# Eitech-Robotics_v10dev.net
KiCad netlist of a schematic drawn in EAGLE
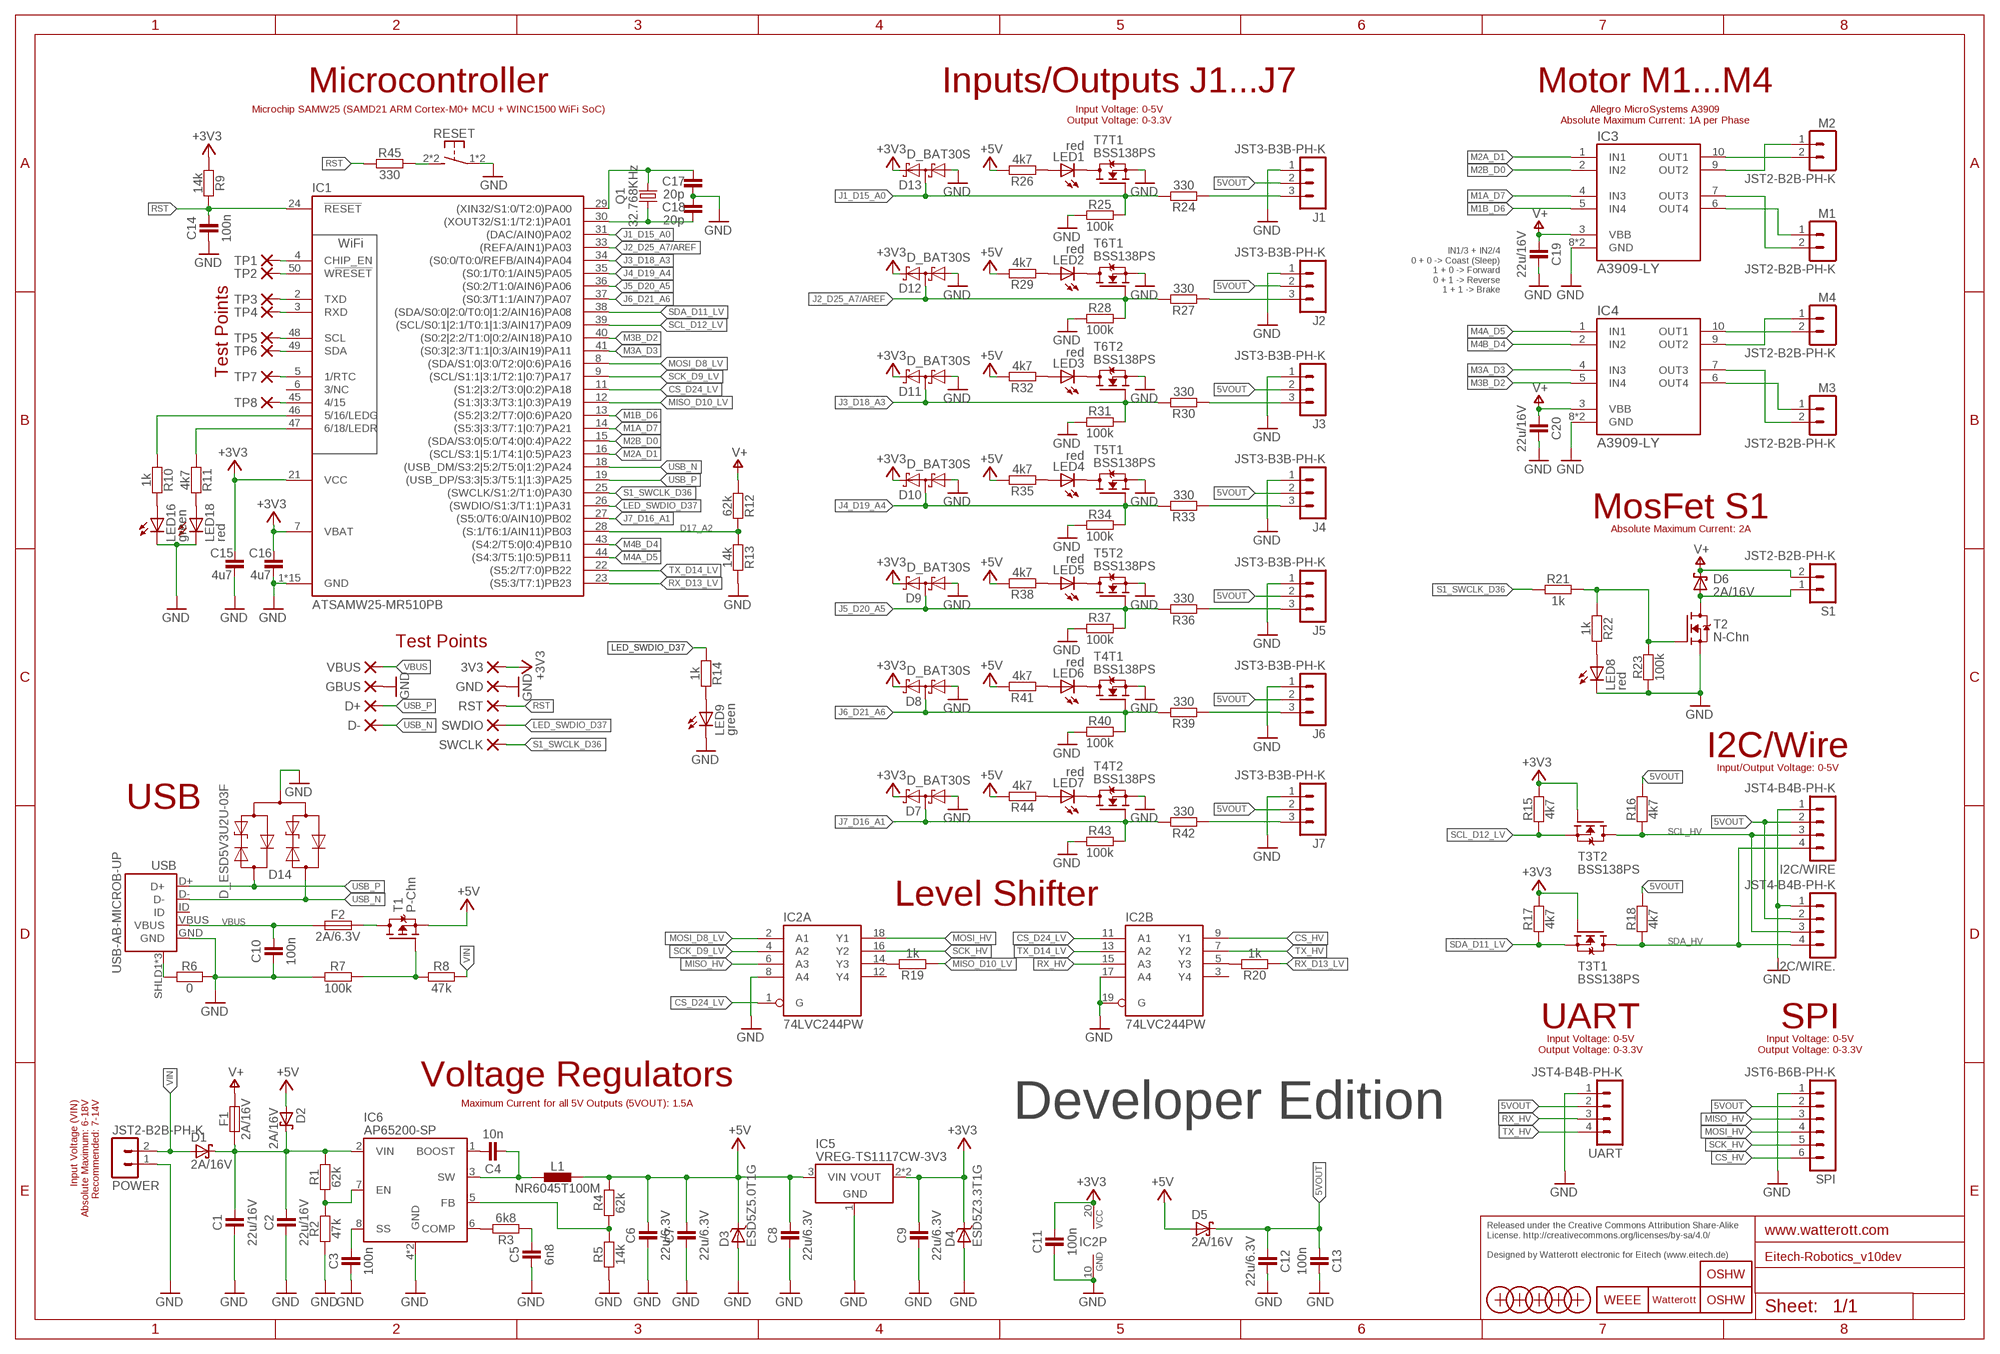
[diagram p0: schematic, sheet 1]

(export (version "E")
  (design (tool "Eeschema 10.0.6"))
  (components
    (comp (ref "3V3")
      (value "PAD-1.0_NC")
      (footprint "eagle-import:PAD-1.0_NC")
      (libsource (lib "eagle-import") (part "PAD-1.0_NC"))
    )
    (comp (ref "C1")
      (value "22u/16V")
      (footprint "eagle-import:C0805")
      (libsource (lib "eagle-import") (part "CAPACITOR-0805"))
    )
    (comp (ref "C2")
      (value "22u/16V")
      (footprint "eagle-import:C0805")
      (libsource (lib "eagle-import") (part "CAPACITOR-0805"))
    )
    (comp (ref "C3")
      (value "100n")
      (footprint "eagle-import:C0402")
      (libsource (lib "eagle-import") (part "CAPACITOR-0402"))
    )
    (comp (ref "C4")
      (value "10n")
      (footprint "eagle-import:C0402")
      (libsource (lib "eagle-import") (part "CAPACITOR-0402"))
    )
    (comp (ref "C5")
      (value "6n8")
      (footprint "eagle-import:C0402")
      (libsource (lib "eagle-import") (part "CAPACITOR-0402"))
    )
    (comp (ref "C6")
      (value "22u/6.3V")
      (footprint "eagle-import:C0805")
      (libsource (lib "eagle-import") (part "CAPACITOR-0805"))
    )
    (comp (ref "C7")
      (value "22u/6.3V")
      (footprint "eagle-import:C0805")
      (libsource (lib "eagle-import") (part "CAPACITOR-0805"))
    )
    (comp (ref "C8")
      (value "22u/6.3V")
      (footprint "eagle-import:C0805")
      (libsource (lib "eagle-import") (part "CAPACITOR-0805"))
    )
    (comp (ref "C9")
      (value "22u/6.3V")
      (footprint "eagle-import:C0805")
      (libsource (lib "eagle-import") (part "CAPACITOR-0805"))
    )
    (comp (ref "C10")
      (value "100n")
      (footprint "eagle-import:C0402")
      (libsource (lib "eagle-import") (part "CAPACITOR-0402"))
    )
    (comp (ref "C11")
      (value "100n")
      (footprint "eagle-import:C0402")
      (libsource (lib "eagle-import") (part "CAPACITOR-0402"))
    )
    (comp (ref "C12")
      (value "22u/6.3V")
      (footprint "eagle-import:C0805")
      (libsource (lib "eagle-import") (part "CAPACITOR-0805"))
    )
    (comp (ref "C13")
      (value "100n")
      (footprint "eagle-import:C0402")
      (libsource (lib "eagle-import") (part "CAPACITOR-0402"))
    )
    (comp (ref "C14")
      (value "100n")
      (footprint "eagle-import:C0402")
      (libsource (lib "eagle-import") (part "CAPACITOR-0402"))
    )
    (comp (ref "C15")
      (value "4u7")
      (footprint "eagle-import:C0603")
      (libsource (lib "eagle-import") (part "CAPACITOR-0603"))
    )
    (comp (ref "C16")
      (value "4u7")
      (footprint "eagle-import:C0603")
      (libsource (lib "eagle-import") (part "CAPACITOR-0603"))
    )
    (comp (ref "C17")
      (value "20p")
      (footprint "eagle-import:C0402")
      (libsource (lib "eagle-import") (part "CAPACITOR-0402"))
    )
    (comp (ref "C18")
      (value "20p")
      (footprint "eagle-import:C0402")
      (libsource (lib "eagle-import") (part "CAPACITOR-0402"))
    )
    (comp (ref "C19")
      (value "22u/16V")
      (footprint "eagle-import:C0805")
      (libsource (lib "eagle-import") (part "CAPACITOR-0805"))
    )
    (comp (ref "C20")
      (value "22u/16V")
      (footprint "eagle-import:C0805")
      (libsource (lib "eagle-import") (part "CAPACITOR-0805"))
    )
    (comp (ref "D+")
      (value "PAD-1.0_NC")
      (footprint "eagle-import:PAD-1.0_NC")
      (libsource (lib "eagle-import") (part "PAD-1.0_NC"))
    )
    (comp (ref "D-")
      (value "PAD-1.0_NC")
      (footprint "eagle-import:PAD-1.0_NC")
      (libsource (lib "eagle-import") (part "PAD-1.0_NC"))
    )
    (comp (ref "D1")
      (value "2A/16V")
      (footprint "eagle-import:SMA_DO214AC")
      (libsource (lib "eagle-import") (part "D_SCHOTTKY-SMA"))
    )
    (comp (ref "D2")
      (value "2A/16V")
      (footprint "eagle-import:SMA_DO214AC")
      (libsource (lib "eagle-import") (part "D_SCHOTTKY-SMA"))
    )
    (comp (ref "D3")
      (value "ESD5Z5.0T1G")
      (footprint "eagle-import:SOD523")
      (libsource (lib "eagle-import") (part "D_TVS-SOD523"))
    )
    (comp (ref "D4")
      (value "ESD5Z3.3T1G")
      (footprint "eagle-import:SOD523")
      (libsource (lib "eagle-import") (part "D_TVS-SOD523"))
    )
    (comp (ref "D5")
      (value "2A/16V")
      (footprint "eagle-import:SMA_DO214AC")
      (libsource (lib "eagle-import") (part "D_SCHOTTKY-SMA"))
    )
    (comp (ref "D6")
      (value "2A/16V")
      (footprint "eagle-import:SMA_DO214AC")
      (libsource (lib "eagle-import") (part "D_SCHOTTKY-SMA"))
    )
    (comp (ref "D7")
      (value "D_BAT30S")
      (footprint "eagle-import:SOT323")
      (libsource (lib "eagle-import") (part "D_BAT30S"))
    )
    (comp (ref "D8")
      (value "D_BAT30S")
      (footprint "eagle-import:SOT323")
      (libsource (lib "eagle-import") (part "D_BAT30S"))
    )
    (comp (ref "D9")
      (value "D_BAT30S")
      (footprint "eagle-import:SOT323")
      (libsource (lib "eagle-import") (part "D_BAT30S"))
    )
    (comp (ref "D10")
      (value "D_BAT30S")
      (footprint "eagle-import:SOT323")
      (libsource (lib "eagle-import") (part "D_BAT30S"))
    )
    (comp (ref "D11")
      (value "D_BAT30S")
      (footprint "eagle-import:SOT323")
      (libsource (lib "eagle-import") (part "D_BAT30S"))
    )
    (comp (ref "D12")
      (value "D_BAT30S")
      (footprint "eagle-import:SOT323")
      (libsource (lib "eagle-import") (part "D_BAT30S"))
    )
    (comp (ref "D13")
      (value "D_BAT30S")
      (footprint "eagle-import:SOT323")
      (libsource (lib "eagle-import") (part "D_BAT30S"))
    )
    (comp (ref "D14")
      (value "D_ESD5V3U2U-03F")
      (footprint "eagle-import:SOT723")
      (libsource (lib "eagle-import") (part "D_ESD5V3U2U-03F"))
    )
    (comp (ref "F1")
      (value "2A/16V")
      (footprint "eagle-import:C1812")
      (libsource (lib "eagle-import") (part "FUSE-1812"))
    )
    (comp (ref "F2")
      (value "2A/6.3V")
      (footprint "eagle-import:C1206")
      (libsource (lib "eagle-import") (part "FUSE-1206"))
    )
    (comp (ref "GBUS")
      (value "PAD-1.0_NC")
      (footprint "eagle-import:PAD-1.0_NC")
      (libsource (lib "eagle-import") (part "PAD-1.0_NC"))
    )
    (comp (ref "GND")
      (value "PAD-1.0_NC")
      (footprint "eagle-import:PAD-1.0_NC")
      (libsource (lib "eagle-import") (part "PAD-1.0_NC"))
    )
    (comp (ref "I2C/WIRE")
      (value "JST4-B4B-PH-K")
      (footprint "eagle-import:JST_B4B-PH-K")
      (libsource (lib "eagle-import") (part "JST4-B4B-PH-K"))
    )
    (comp (ref "I2C/WIRE.")
      (value "JST4-B4B-PH-K")
      (footprint "eagle-import:JST_B4B-PH-K")
      (libsource (lib "eagle-import") (part "JST4-B4B-PH-K"))
    )
    (comp (ref "IC1")
      (value "ATSAMW25-MR510PB")
      (footprint "eagle-import:ATSAMW25-MRX10")
      (libsource (lib "eagle-import") (part "ATSAMW25-MR510PB"))
    )
    (comp (ref "IC2")
      (value "74LVC244PW")
      (footprint "eagle-import:TSSOP20")
      (libsource (lib "eagle-import") (part "74244PWLVC"))
    )
    (comp (ref "IC3")
      (value "A3909-LY")
      (footprint "eagle-import:MSOP10-PAD")
      (libsource (lib "eagle-import") (part "A3909-LY"))
    )
    (comp (ref "IC4")
      (value "A3909-LY")
      (footprint "eagle-import:MSOP10-PAD")
      (libsource (lib "eagle-import") (part "A3909-LY"))
    )
    (comp (ref "IC5")
      (value "VREG-TS1117CW-3V3")
      (footprint "eagle-import:SOT223")
      (libsource (lib "eagle-import") (part "VREG-TS1117CW-3V3"))
    )
    (comp (ref "IC6")
      (value "AP65200-SP")
      (footprint "eagle-import:SO08-PAD")
      (libsource (lib "eagle-import") (part "AP65200-SP"))
    )
    (comp (ref "J1")
      (value "JST3-B3B-PH-K")
      (footprint "eagle-import:JST_B3B-PH-K")
      (libsource (lib "eagle-import") (part "JST3-B3B-PH-K"))
    )
    (comp (ref "J2")
      (value "JST3-B3B-PH-K")
      (footprint "eagle-import:JST_B3B-PH-K")
      (libsource (lib "eagle-import") (part "JST3-B3B-PH-K"))
    )
    (comp (ref "J3")
      (value "JST3-B3B-PH-K")
      (footprint "eagle-import:JST_B3B-PH-K")
      (libsource (lib "eagle-import") (part "JST3-B3B-PH-K"))
    )
    (comp (ref "J4")
      (value "JST3-B3B-PH-K")
      (footprint "eagle-import:JST_B3B-PH-K")
      (libsource (lib "eagle-import") (part "JST3-B3B-PH-K"))
    )
    (comp (ref "J5")
      (value "JST3-B3B-PH-K")
      (footprint "eagle-import:JST_B3B-PH-K")
      (libsource (lib "eagle-import") (part "JST3-B3B-PH-K"))
    )
    (comp (ref "J6")
      (value "JST3-B3B-PH-K")
      (footprint "eagle-import:JST_B3B-PH-K")
      (libsource (lib "eagle-import") (part "JST3-B3B-PH-K"))
    )
    (comp (ref "J7")
      (value "JST3-B3B-PH-K")
      (footprint "eagle-import:JST_B3B-PH-K")
      (libsource (lib "eagle-import") (part "JST3-B3B-PH-K"))
    )
    (comp (ref "L1")
      (value "NR6045T100M")
      (footprint "eagle-import:L_NR60XX")
      (libsource (lib "eagle-import") (part "INDUCTOR-NR60XX"))
    )
    (comp (ref "LED1")
      (value "red")
      (footprint "eagle-import:C0603")
      (libsource (lib "eagle-import") (part "LED-0603"))
    )
    (comp (ref "LED2")
      (value "red")
      (footprint "eagle-import:C0603")
      (libsource (lib "eagle-import") (part "LED-0603"))
    )
    (comp (ref "LED3")
      (value "red")
      (footprint "eagle-import:C0603")
      (libsource (lib "eagle-import") (part "LED-0603"))
    )
    (comp (ref "LED4")
      (value "red")
      (footprint "eagle-import:C0603")
      (libsource (lib "eagle-import") (part "LED-0603"))
    )
    (comp (ref "LED5")
      (value "red")
      (footprint "eagle-import:C0603")
      (libsource (lib "eagle-import") (part "LED-0603"))
    )
    (comp (ref "LED6")
      (value "red")
      (footprint "eagle-import:C0603")
      (libsource (lib "eagle-import") (part "LED-0603"))
    )
    (comp (ref "LED7")
      (value "red")
      (footprint "eagle-import:C0603")
      (libsource (lib "eagle-import") (part "LED-0603"))
    )
    (comp (ref "LED8")
      (value "red")
      (footprint "eagle-import:C0603")
      (libsource (lib "eagle-import") (part "LED-0603"))
    )
    (comp (ref "LED9")
      (value "green")
      (footprint "eagle-import:C0603")
      (libsource (lib "eagle-import") (part "LED-0603"))
    )
    (comp (ref "LED16")
      (value "green")
      (footprint "eagle-import:C0603")
      (libsource (lib "eagle-import") (part "LED-0603"))
    )
    (comp (ref "LED18")
      (value "red")
      (footprint "eagle-import:C0603")
      (libsource (lib "eagle-import") (part "LED-0603"))
    )
    (comp (ref "LOGO1")
      (value "OSHW_LOGOX0100")
      (footprint "eagle-import:OSHW_6X100")
      (libsource (lib "eagle-import") (part "OSHW_LOGOX0100"))
    )
    (comp (ref "LOGO2")
      (value "WEEE_LOGO-S")
      (footprint "eagle-import:WEEE_TPLAC_S")
      (libsource (lib "eagle-import") (part "WEEE_LOGO-S"))
    )
    (comp (ref "LOGO3")
      (value "LOGO-S_PLACE_S")
      (footprint "eagle-import:SPARK_TPLACE_S")
      (libsource (lib "eagle-import") (part "LOGO-S_PLACE_S"))
    )
    (comp (ref "LOGO4")
      (value "OSHW_LOGOX0150")
      (footprint "eagle-import:OSHW_6X150")
      (libsource (lib "eagle-import") (part "OSHW_LOGOX0150"))
    )
    (comp (ref "M1")
      (value "JST2-B2B-PH-K")
      (footprint "eagle-import:JST_B2B-PH-K")
      (libsource (lib "eagle-import") (part "JST2-B2B-PH-K"))
    )
    (comp (ref "M2")
      (value "JST2-B2B-PH-K")
      (footprint "eagle-import:JST_B2B-PH-K")
      (libsource (lib "eagle-import") (part "JST2-B2B-PH-K"))
    )
    (comp (ref "M3")
      (value "JST2-B2B-PH-K")
      (footprint "eagle-import:JST_B2B-PH-K")
      (libsource (lib "eagle-import") (part "JST2-B2B-PH-K"))
    )
    (comp (ref "M4")
      (value "JST2-B2B-PH-K")
      (footprint "eagle-import:JST_B2B-PH-K")
      (libsource (lib "eagle-import") (part "JST2-B2B-PH-K"))
    )
    (comp (ref "POWER")
      (value "JST2-B2B-PH-K")
      (footprint "eagle-import:JST_B2B-PH-K")
      (libsource (lib "eagle-import") (part "JST2-B2B-PH-K"))
    )
    (comp (ref "Q1")
      (value "32.768KHz")
      (footprint "eagle-import:CRYSTAL_ZM315")
      (libsource (lib "eagle-import") (part "CRYSTAL-ZM315"))
    )
    (comp (ref "R1")
      (value "62k")
      (footprint "eagle-import:C0402")
      (libsource (lib "eagle-import") (part "RESISTOR-0402"))
    )
    (comp (ref "R2")
      (value "47k")
      (footprint "eagle-import:C0402")
      (libsource (lib "eagle-import") (part "RESISTOR-0402"))
    )
    (comp (ref "R3")
      (value "6k8")
      (footprint "eagle-import:C0402")
      (libsource (lib "eagle-import") (part "RESISTOR-0402"))
    )
    (comp (ref "R4")
      (value "62k")
      (footprint "eagle-import:C0402")
      (libsource (lib "eagle-import") (part "RESISTOR-0402"))
    )
    (comp (ref "R5")
      (value "14k")
      (footprint "eagle-import:C0402")
      (libsource (lib "eagle-import") (part "RESISTOR-0402"))
    )
    (comp (ref "R6")
      (value "0")
      (footprint "eagle-import:C0402")
      (libsource (lib "eagle-import") (part "RESISTOR-0402"))
    )
    (comp (ref "R7")
      (value "100k")
      (footprint "eagle-import:C0402")
      (libsource (lib "eagle-import") (part "RESISTOR-0402"))
    )
    (comp (ref "R8")
      (value "47k")
      (footprint "eagle-import:C0402")
      (libsource (lib "eagle-import") (part "RESISTOR-0402"))
    )
    (comp (ref "R9")
      (value "14k")
      (footprint "eagle-import:C0402")
      (libsource (lib "eagle-import") (part "RESISTOR-0402"))
    )
    (comp (ref "R10")
      (value "1k")
      (footprint "eagle-import:C0402")
      (libsource (lib "eagle-import") (part "RESISTOR-0402"))
    )
    (comp (ref "R11")
      (value "4k7")
      (footprint "eagle-import:C0402")
      (libsource (lib "eagle-import") (part "RESISTOR-0402"))
    )
    (comp (ref "R12")
      (value "62k")
      (footprint "eagle-import:C0402")
      (libsource (lib "eagle-import") (part "RESISTOR-0402"))
    )
    (comp (ref "R13")
      (value "14k")
      (footprint "eagle-import:C0402")
      (libsource (lib "eagle-import") (part "RESISTOR-0402"))
    )
    (comp (ref "R14")
      (value "1k")
      (footprint "eagle-import:C0402")
      (libsource (lib "eagle-import") (part "RESISTOR-0402"))
    )
    (comp (ref "R15")
      (value "4k7")
      (footprint "eagle-import:C0402")
      (libsource (lib "eagle-import") (part "RESISTOR-0402"))
    )
    (comp (ref "R16")
      (value "4k7")
      (footprint "eagle-import:C0402")
      (libsource (lib "eagle-import") (part "RESISTOR-0402"))
    )
    (comp (ref "R17")
      (value "4k7")
      (footprint "eagle-import:C0402")
      (libsource (lib "eagle-import") (part "RESISTOR-0402"))
    )
    (comp (ref "R18")
      (value "4k7")
      (footprint "eagle-import:C0402")
      (libsource (lib "eagle-import") (part "RESISTOR-0402"))
    )
    (comp (ref "R19")
      (value "1k")
      (footprint "eagle-import:C0402")
      (libsource (lib "eagle-import") (part "RESISTOR-0402"))
    )
    (comp (ref "R20")
      (value "1k")
      (footprint "eagle-import:C0402")
      (libsource (lib "eagle-import") (part "RESISTOR-0402"))
    )
    (comp (ref "R21")
      (value "1k")
      (footprint "eagle-import:C0402")
      (libsource (lib "eagle-import") (part "RESISTOR-0402"))
    )
    (comp (ref "R22")
      (value "1k")
      (footprint "eagle-import:C0402")
      (libsource (lib "eagle-import") (part "RESISTOR-0402"))
    )
    (comp (ref "R23")
      (value "100k")
      (footprint "eagle-import:C0402")
      (libsource (lib "eagle-import") (part "RESISTOR-0402"))
    )
    (comp (ref "R24")
      (value "330")
      (footprint "eagle-import:C0402")
      (libsource (lib "eagle-import") (part "RESISTOR-0402"))
    )
    (comp (ref "R25")
      (value "100k")
      (footprint "eagle-import:C0402")
      (libsource (lib "eagle-import") (part "RESISTOR-0402"))
    )
    (comp (ref "R26")
      (value "4k7")
      (footprint "eagle-import:C0402")
      (libsource (lib "eagle-import") (part "RESISTOR-0402"))
    )
    (comp (ref "R27")
      (value "330")
      (footprint "eagle-import:C0402")
      (libsource (lib "eagle-import") (part "RESISTOR-0402"))
    )
    (comp (ref "R28")
      (value "100k")
      (footprint "eagle-import:C0402")
      (libsource (lib "eagle-import") (part "RESISTOR-0402"))
    )
    (comp (ref "R29")
      (value "4k7")
      (footprint "eagle-import:C0402")
      (libsource (lib "eagle-import") (part "RESISTOR-0402"))
    )
    (comp (ref "R30")
      (value "330")
      (footprint "eagle-import:C0402")
      (libsource (lib "eagle-import") (part "RESISTOR-0402"))
    )
    (comp (ref "R31")
      (value "100k")
      (footprint "eagle-import:C0402")
      (libsource (lib "eagle-import") (part "RESISTOR-0402"))
    )
    (comp (ref "R32")
      (value "4k7")
      (footprint "eagle-import:C0402")
      (libsource (lib "eagle-import") (part "RESISTOR-0402"))
    )
    (comp (ref "R33")
      (value "330")
      (footprint "eagle-import:C0402")
      (libsource (lib "eagle-import") (part "RESISTOR-0402"))
    )
    (comp (ref "R34")
      (value "100k")
      (footprint "eagle-import:C0402")
      (libsource (lib "eagle-import") (part "RESISTOR-0402"))
    )
    (comp (ref "R35")
      (value "4k7")
      (footprint "eagle-import:C0402")
      (libsource (lib "eagle-import") (part "RESISTOR-0402"))
    )
    (comp (ref "R36")
      (value "330")
      (footprint "eagle-import:C0402")
      (libsource (lib "eagle-import") (part "RESISTOR-0402"))
    )
    (comp (ref "R37")
      (value "100k")
      (footprint "eagle-import:C0402")
      (libsource (lib "eagle-import") (part "RESISTOR-0402"))
    )
    (comp (ref "R38")
      (value "4k7")
      (footprint "eagle-import:C0402")
      (libsource (lib "eagle-import") (part "RESISTOR-0402"))
    )
    (comp (ref "R39")
      (value "330")
      (footprint "eagle-import:C0402")
      (libsource (lib "eagle-import") (part "RESISTOR-0402"))
    )
    (comp (ref "R40")
      (value "100k")
      (footprint "eagle-import:C0402")
      (libsource (lib "eagle-import") (part "RESISTOR-0402"))
    )
    (comp (ref "R41")
      (value "4k7")
      (footprint "eagle-import:C0402")
      (libsource (lib "eagle-import") (part "RESISTOR-0402"))
    )
    (comp (ref "R42")
      (value "330")
      (footprint "eagle-import:C0402")
      (libsource (lib "eagle-import") (part "RESISTOR-0402"))
    )
    (comp (ref "R43")
      (value "100k")
      (footprint "eagle-import:C0402")
      (libsource (lib "eagle-import") (part "RESISTOR-0402"))
    )
    (comp (ref "R44")
      (value "4k7")
      (footprint "eagle-import:C0402")
      (libsource (lib "eagle-import") (part "RESISTOR-0402"))
    )
    (comp (ref "R45")
      (value "330")
      (footprint "eagle-import:C0402")
      (libsource (lib "eagle-import") (part "RESISTOR-0402"))
    )
    (comp (ref "RESET")
      (value "SW-TACTILE-TL3305C")
      (footprint "eagle-import:TL3305")
      (fields (field (name "MPN") "TL3305C"))
      (libsource (lib "eagle-import") (part "SW-TACTILE-TL3305"))
    )
    (comp (ref "RST")
      (value "PAD-1.0_NC")
      (footprint "eagle-import:PAD-1.0_NC")
      (libsource (lib "eagle-import") (part "PAD-1.0_NC"))
    )
    (comp (ref "S1")
      (value "JST2-B2B-PH-K")
      (footprint "eagle-import:JST_B2B-PH-K")
      (libsource (lib "eagle-import") (part "JST2-B2B-PH-K"))
    )
    (comp (ref "SPI")
      (value "JST6-B6B-PH-K")
      (footprint "eagle-import:JST_B6B-PH-K")
      (libsource (lib "eagle-import") (part "JST6-B6B-PH-K"))
    )
    (comp (ref "SWCLK")
      (value "PAD-1.0_NC")
      (footprint "eagle-import:PAD-1.0_NC")
      (libsource (lib "eagle-import") (part "PAD-1.0_NC"))
    )
    (comp (ref "SWDIO")
      (value "PAD-1.0_NC")
      (footprint "eagle-import:PAD-1.0_NC")
      (libsource (lib "eagle-import") (part "PAD-1.0_NC"))
    )
    (comp (ref "T1")
      (value "P-Chn")
      (footprint "eagle-import:SOT23")
      (libsource (lib "eagle-import") (part "MOSFET-P-SOT23"))
    )
    (comp (ref "T2")
      (value "N-Chn")
      (footprint "eagle-import:SOT23")
      (libsource (lib "eagle-import") (part "MOSFET-N-SOT23"))
    )
    (comp (ref "T3")
      (value "BSS138PS")
      (footprint "eagle-import:SOT363")
      (libsource (lib "eagle-import") (part "BSS138PS"))
    )
    (comp (ref "T4")
      (value "BSS138PS")
      (footprint "eagle-import:SOT363")
      (libsource (lib "eagle-import") (part "BSS138PS"))
    )
    (comp (ref "T5")
      (value "BSS138PS")
      (footprint "eagle-import:SOT363")
      (libsource (lib "eagle-import") (part "BSS138PS"))
    )
    (comp (ref "T6")
      (value "BSS138PS")
      (footprint "eagle-import:SOT363")
      (libsource (lib "eagle-import") (part "BSS138PS"))
    )
    (comp (ref "T7")
      (value "BSS138PS")
      (footprint "eagle-import:SOT363")
      (libsource (lib "eagle-import") (part "BSS138PS"))
    )
    (comp (ref "TP1")
      (value "PAD-0.7_NC")
      (footprint "eagle-import:PAD-0.7_NC")
      (libsource (lib "eagle-import") (part "PAD-0.7_NC"))
    )
    (comp (ref "TP2")
      (value "PAD-0.7_NC")
      (footprint "eagle-import:PAD-0.7_NC")
      (libsource (lib "eagle-import") (part "PAD-0.7_NC"))
    )
    (comp (ref "TP3")
      (value "PAD-0.7_NC")
      (footprint "eagle-import:PAD-0.7_NC")
      (libsource (lib "eagle-import") (part "PAD-0.7_NC"))
    )
    (comp (ref "TP4")
      (value "PAD-0.7_NC")
      (footprint "eagle-import:PAD-0.7_NC")
      (libsource (lib "eagle-import") (part "PAD-0.7_NC"))
    )
    (comp (ref "TP5")
      (value "PAD-0.7_NC")
      (footprint "eagle-import:PAD-0.7_NC")
      (libsource (lib "eagle-import") (part "PAD-0.7_NC"))
    )
    (comp (ref "TP6")
      (value "PAD-0.7_NC")
      (footprint "eagle-import:PAD-0.7_NC")
      (libsource (lib "eagle-import") (part "PAD-0.7_NC"))
    )
    (comp (ref "TP7")
      (value "PAD-0.7_NC")
      (footprint "eagle-import:PAD-0.7_NC")
      (libsource (lib "eagle-import") (part "PAD-0.7_NC"))
    )
    (comp (ref "TP8")
      (value "PAD-0.7_NC")
      (footprint "eagle-import:PAD-0.7_NC")
      (libsource (lib "eagle-import") (part "PAD-0.7_NC"))
    )
    (comp (ref "UART")
      (value "JST4-B4B-PH-K")
      (footprint "eagle-import:JST_B4B-PH-K")
      (libsource (lib "eagle-import") (part "JST4-B4B-PH-K"))
    )
    (comp (ref "USB")
      (value "USB-AB-MICROB-UP")
      (footprint "eagle-import:USB-MICROB-1051330011")
      (libsource (lib "eagle-import") (part "USB-AB-MICROB-UP"))
    )
    (comp (ref "VBUS")
      (value "PAD-1.0_NC")
      (footprint "eagle-import:PAD-1.0_NC")
      (libsource (lib "eagle-import") (part "PAD-1.0_NC"))
    )
    (comp (ref "X1")
      (value "PASSER-07")
      (footprint "eagle-import:PASSER_07MM")
      (libsource (lib "eagle-import") (part "PASSER-07"))
    )
    (comp (ref "X2")
      (value "PASSER-07")
      (footprint "eagle-import:PASSER_07MM")
      (libsource (lib "eagle-import") (part "PASSER-07"))
    )
    (comp (ref "X3")
      (value "PASSER-07")
      (footprint "eagle-import:PASSER_07MM")
      (libsource (lib "eagle-import") (part "PASSER-07"))
    )
    (comp (ref "X4")
      (value "PASSER-07")
      (footprint "eagle-import:PASSER_07MM")
      (libsource (lib "eagle-import") (part "PASSER-07"))
    )
    (comp (ref "X5")
      (value "PASSER-04")
      (footprint "eagle-import:PASSER_04MM")
      (libsource (lib "eagle-import") (part "PASSER-04"))
    )
  )
  (nets
    (net (code "1") (name "+3V3") (class "Default")
      (node (ref "3V3") (pin "1") (pinfunction "P_1") (pintype "passive"))
      (node (ref "C11") (pin "2") (pinfunction "2_2") (pintype "passive"))
      (node (ref "C15") (pin "2") (pinfunction "2_2") (pintype "passive"))
      (node (ref "C16") (pin "2") (pinfunction "2_2") (pintype "passive"))
      (node (ref "C9") (pin "2") (pinfunction "2_2") (pintype "passive"))
      (node (ref "D10") (pin "2") (pinfunction "C_2") (pintype "passive"))
      (node (ref "D11") (pin "2") (pinfunction "C_2") (pintype "passive"))
      (node (ref "D12") (pin "2") (pinfunction "C_2") (pintype "passive"))
      (node (ref "D13") (pin "2") (pinfunction "C_2") (pintype "passive"))
      (node (ref "D4") (pin "C") (pinfunction "C_C") (pintype "passive"))
      (node (ref "D7") (pin "2") (pinfunction "C_2") (pintype "passive"))
      (node (ref "D8") (pin "2") (pinfunction "C_2") (pintype "passive"))
      (node (ref "D9") (pin "2") (pinfunction "C_2") (pintype "passive"))
      (node (ref "IC1") (pin "21") (pinfunction "VCC_21") (pintype "power_in"))
      (node (ref "IC1") (pin "7") (pinfunction "VBAT_7") (pintype "power_in"))
      (node (ref "IC2") (pin "20") (pinfunction "VCC_20") (pintype "power_in"))
      (node (ref "IC5") (pin "2") (pinfunction "VOUT_2") (pintype "power_in"))
      (node (ref "IC5") (pin "4") (pinfunction "VOUT_4") (pintype "power_in"))
      (node (ref "R15") (pin "2") (pinfunction "2_2") (pintype "passive"))
      (node (ref "R17") (pin "2") (pinfunction "2_2") (pintype "passive"))
      (node (ref "R9") (pin "1") (pinfunction "1_1") (pintype "passive"))
      (node (ref "T3") (pin "2") (pinfunction "G_2") (pintype "passive"))
      (node (ref "T3") (pin "5") (pinfunction "G_5") (pintype "passive"))
    )
    (net (code "2") (name "+5V") (class "Default")
      (node (ref "C6") (pin "2") (pinfunction "2_2") (pintype "passive"))
      (node (ref "C7") (pin "2") (pinfunction "2_2") (pintype "passive"))
      (node (ref "C8") (pin "2") (pinfunction "2_2") (pintype "passive"))
      (node (ref "D2") (pin "A") (pinfunction "A_A") (pintype "passive"))
      (node (ref "D3") (pin "C") (pinfunction "C_C") (pintype "passive"))
      (node (ref "D5") (pin "A") (pinfunction "A_A") (pintype "passive"))
      (node (ref "IC5") (pin "3") (pinfunction "VIN_3") (pintype "power_in"))
      (node (ref "L1") (pin "2") (pinfunction "2_2") (pintype "passive"))
      (node (ref "R26") (pin "2") (pinfunction "2_2") (pintype "passive"))
      (node (ref "R29") (pin "2") (pinfunction "2_2") (pintype "passive"))
      (node (ref "R32") (pin "2") (pinfunction "2_2") (pintype "passive"))
      (node (ref "R35") (pin "2") (pinfunction "2_2") (pintype "passive"))
      (node (ref "R38") (pin "2") (pinfunction "2_2") (pintype "passive"))
      (node (ref "R4") (pin "2") (pinfunction "2_2") (pintype "passive"))
      (node (ref "R41") (pin "2") (pinfunction "2_2") (pintype "passive"))
      (node (ref "R44") (pin "2") (pinfunction "2_2") (pintype "passive"))
      (node (ref "T1") (pin "2") (pinfunction "S_2") (pintype "passive"))
    )
    (net (code "3") (name "/D17_A2") (class "Default")
      (node (ref "IC1") (pin "28") (pinfunction "(S:1/T6:1/AIN11)PB03_28") (pintype "bidirectional"))
      (node (ref "R12") (pin "2") (pinfunction "2_2") (pintype "passive"))
      (node (ref "R13") (pin "1") (pinfunction "1_1") (pintype "passive"))
    )
    (net (code "4") (name "/SCL_HV") (class "Default")
      (node (ref "I2C/WIRE") (pin "3") (pinfunction "3_3") (pintype "passive"))
      (node (ref "I2C/WIRE.") (pin "3") (pinfunction "3_3") (pintype "passive"))
      (node (ref "R16") (pin "1") (pinfunction "1_1") (pintype "passive"))
      (node (ref "T3") (pin "3") (pinfunction "D_3") (pintype "passive"))
    )
    (net (code "5") (name "/SDA_HV") (class "Default")
      (node (ref "I2C/WIRE") (pin "4") (pinfunction "4_4") (pintype "passive"))
      (node (ref "I2C/WIRE.") (pin "4") (pinfunction "4_4") (pintype "passive"))
      (node (ref "R18") (pin "1") (pinfunction "1_1") (pintype "passive"))
      (node (ref "T3") (pin "6") (pinfunction "D_6") (pintype "passive"))
    )
    (net (code "6") (name "5VOUT") (class "Default")
      (node (ref "C12") (pin "2") (pinfunction "2_2") (pintype "passive"))
      (node (ref "C13") (pin "2") (pinfunction "2_2") (pintype "passive"))
      (node (ref "D5") (pin "C") (pinfunction "C_C") (pintype "passive"))
      (node (ref "I2C/WIRE") (pin "2") (pinfunction "2_2") (pintype "passive"))
      (node (ref "I2C/WIRE.") (pin "2") (pinfunction "2_2") (pintype "passive"))
      (node (ref "J1") (pin "2") (pinfunction "2_2") (pintype "passive"))
      (node (ref "J2") (pin "2") (pinfunction "2_2") (pintype "passive"))
      (node (ref "J3") (pin "2") (pinfunction "2_2") (pintype "passive"))
      (node (ref "J4") (pin "2") (pinfunction "2_2") (pintype "passive"))
      (node (ref "J5") (pin "2") (pinfunction "2_2") (pintype "passive"))
      (node (ref "J6") (pin "2") (pinfunction "2_2") (pintype "passive"))
      (node (ref "J7") (pin "2") (pinfunction "2_2") (pintype "passive"))
      (node (ref "R16") (pin "2") (pinfunction "2_2") (pintype "passive"))
      (node (ref "R18") (pin "2") (pinfunction "2_2") (pintype "passive"))
      (node (ref "SPI") (pin "2") (pinfunction "2_2") (pintype "passive"))
      (node (ref "UART") (pin "2") (pinfunction "2_2") (pintype "passive"))
    )
    (net (code "7") (name "CS_D24_LV") (class "Default")
      (node (ref "IC1") (pin "11") (pinfunction "(S1:2|3:2/T3:0|0:2)PA18_11") (pintype "bidirectional"))
      (node (ref "IC2") (pin "1") (pinfunction "G_1") (pintype "input"))
      (node (ref "IC2") (pin "11") (pinfunction "A1_11") (pintype "input"))
    )
    (net (code "8") (name "CS_HV") (class "Default")
      (node (ref "IC2") (pin "9") (pinfunction "Y1_9") (pintype "tri_state"))
      (node (ref "SPI") (pin "6") (pinfunction "6_6") (pintype "passive"))
    )
    (net (code "9") (name "GND") (class "Default")
      (node (ref "C1") (pin "1") (pinfunction "1_1") (pintype "passive"))
      (node (ref "C10") (pin "1") (pinfunction "1_1") (pintype "passive"))
      (node (ref "C11") (pin "1") (pinfunction "1_1") (pintype "passive"))
      (node (ref "C12") (pin "1") (pinfunction "1_1") (pintype "passive"))
      (node (ref "C13") (pin "1") (pinfunction "1_1") (pintype "passive"))
      (node (ref "C14") (pin "1") (pinfunction "1_1") (pintype "passive"))
      (node (ref "C15") (pin "1") (pinfunction "1_1") (pintype "passive"))
      (node (ref "C16") (pin "1") (pinfunction "1_1") (pintype "passive"))
      (node (ref "C17") (pin "2") (pinfunction "2_2") (pintype "passive"))
      (node (ref "C18") (pin "2") (pinfunction "2_2") (pintype "passive"))
      (node (ref "C19") (pin "2") (pinfunction "2_2") (pintype "passive"))
      (node (ref "C2") (pin "1") (pinfunction "1_1") (pintype "passive"))
      (node (ref "C20") (pin "2") (pinfunction "2_2") (pintype "passive"))
      (node (ref "C3") (pin "1") (pinfunction "1_1") (pintype "passive"))
      (node (ref "C5") (pin "1") (pinfunction "1_1") (pintype "passive"))
      (node (ref "C6") (pin "1") (pinfunction "1_1") (pintype "passive"))
      (node (ref "C7") (pin "1") (pinfunction "1_1") (pintype "passive"))
      (node (ref "C8") (pin "1") (pinfunction "1_1") (pintype "passive"))
      (node (ref "C9") (pin "1") (pinfunction "1_1") (pintype "passive"))
      (node (ref "D10") (pin "1") (pinfunction "A_1") (pintype "passive"))
      (node (ref "D11") (pin "1") (pinfunction "A_1") (pintype "passive"))
      (node (ref "D12") (pin "1") (pinfunction "A_1") (pintype "passive"))
      (node (ref "D13") (pin "1") (pinfunction "A_1") (pintype "passive"))
      (node (ref "D14") (pin "3") (pinfunction "A_3") (pintype "passive"))
      (node (ref "D3") (pin "A") (pinfunction "A_A") (pintype "passive"))
      (node (ref "D4") (pin "A") (pinfunction "A_A") (pintype "passive"))
      (node (ref "D7") (pin "1") (pinfunction "A_1") (pintype "passive"))
      (node (ref "D8") (pin "1") (pinfunction "A_1") (pintype "passive"))
      (node (ref "D9") (pin "1") (pinfunction "A_1") (pintype "passive"))
      (node (ref "GBUS") (pin "1") (pinfunction "P_1") (pintype "passive"))
      (node (ref "GND") (pin "1") (pinfunction "P_1") (pintype "passive"))
      (node (ref "I2C/WIRE") (pin "1") (pinfunction "1_1") (pintype "passive"))
      (node (ref "I2C/WIRE.") (pin "1") (pinfunction "1_1") (pintype "passive"))
      (node (ref "IC1") (pin "1") (pinfunction "GND_1") (pintype "power_in"))
      (node (ref "IC1") (pin "10") (pinfunction "GND_10") (pintype "power_in"))
      (node (ref "IC1") (pin "17") (pinfunction "GND_17") (pintype "power_in"))
      (node (ref "IC1") (pin "20") (pinfunction "GND_20") (pintype "power_in"))
      (node (ref "IC1") (pin "32") (pinfunction "GND_32") (pintype "power_in"))
      (node (ref "IC1") (pin "42") (pinfunction "GND_42") (pintype "power_in"))
      (node (ref "IC1") (pin "51") (pinfunction "GND_51") (pintype "power_in"))
      (node (ref "IC1") (pin "GND@1") (pinfunction "GND_GND@1") (pintype "power_in"))
      (node (ref "IC1") (pin "GND@2") (pinfunction "GND_GND@2") (pintype "power_in"))
      (node (ref "IC1") (pin "GND@3") (pinfunction "GND_GND@3") (pintype "power_in"))
      (node (ref "IC1") (pin "GND@4") (pinfunction "GND_GND@4") (pintype "power_in"))
      (node (ref "IC1") (pin "GND@5") (pinfunction "GND_GND@5") (pintype "power_in"))
      (node (ref "IC1") (pin "GND@6") (pinfunction "GND_GND@6") (pintype "power_in"))
      (node (ref "IC1") (pin "GND@7") (pinfunction "GND_GND@7") (pintype "power_in"))
      (node (ref "IC1") (pin "GND@8") (pinfunction "GND_GND@8") (pintype "power_in"))
      (node (ref "IC2") (pin "10") (pinfunction "GND_10") (pintype "power_in"))
      (node (ref "IC2") (pin "17") (pinfunction "A4_17") (pintype "input"))
      (node (ref "IC2") (pin "19") (pinfunction "G_19") (pintype "input"))
      (node (ref "IC2") (pin "8") (pinfunction "A4_8") (pintype "input"))
      (node (ref "IC3") (pin "8") (pinfunction "GND_8") (pintype "power_in"))
      (node (ref "IC3") (pin "TP") (pinfunction "GND_TP") (pintype "power_in"))
      (node (ref "IC4") (pin "8") (pinfunction "GND_8") (pintype "power_in"))
      (node (ref "IC4") (pin "TP") (pinfunction "GND_TP") (pintype "power_in"))
      (node (ref "IC5") (pin "1") (pinfunction "GND_1") (pintype "power_in"))
      (node (ref "IC6") (pin "4") (pinfunction "GND_4") (pintype "power_in"))
      (node (ref "IC6") (pin "TP") (pinfunction "GND_TP") (pintype "power_in"))
      (node (ref "J1") (pin "1") (pinfunction "1_1") (pintype "passive"))
      (node (ref "J2") (pin "1") (pinfunction "1_1") (pintype "passive"))
      (node (ref "J3") (pin "1") (pinfunction "1_1") (pintype "passive"))
      (node (ref "J4") (pin "1") (pinfunction "1_1") (pintype "passive"))
      (node (ref "J5") (pin "1") (pinfunction "1_1") (pintype "passive"))
      (node (ref "J6") (pin "1") (pinfunction "1_1") (pintype "passive"))
      (node (ref "J7") (pin "1") (pinfunction "1_1") (pintype "passive"))
      (node (ref "LED16") (pin "C") (pinfunction "C_C") (pintype "passive"))
      (node (ref "LED18") (pin "C") (pinfunction "C_C") (pintype "passive"))
      (node (ref "LED8") (pin "C") (pinfunction "C_C") (pintype "passive"))
      (node (ref "LED9") (pin "C") (pinfunction "C_C") (pintype "passive"))
      (node (ref "POWER") (pin "1") (pinfunction "2_1") (pintype "passive"))
      (node (ref "R13") (pin "2") (pinfunction "2_2") (pintype "passive"))
      (node (ref "R2") (pin "1") (pinfunction "1_1") (pintype "passive"))
      (node (ref "R23") (pin "1") (pinfunction "1_1") (pintype "passive"))
      (node (ref "R25") (pin "1") (pinfunction "1_1") (pintype "passive"))
      (node (ref "R28") (pin "1") (pinfunction "1_1") (pintype "passive"))
      (node (ref "R31") (pin "1") (pinfunction "1_1") (pintype "passive"))
      (node (ref "R34") (pin "1") (pinfunction "1_1") (pintype "passive"))
      (node (ref "R37") (pin "1") (pinfunction "1_1") (pintype "passive"))
      (node (ref "R40") (pin "1") (pinfunction "1_1") (pintype "passive"))
      (node (ref "R43") (pin "1") (pinfunction "1_1") (pintype "passive"))
      (node (ref "R5") (pin "1") (pinfunction "1_1") (pintype "passive"))
      (node (ref "R6") (pin "1") (pinfunction "1_1") (pintype "passive"))
      (node (ref "R7") (pin "1") (pinfunction "1_1") (pintype "passive"))
      (node (ref "RESET") (pin "1") (pinfunction "P1_1") (pintype "passive"))
      (node (ref "RESET") (pin "4") (pinfunction "P1_4") (pintype "passive"))
      (node (ref "SPI") (pin "1") (pinfunction "1_1") (pintype "passive"))
      (node (ref "T2") (pin "2") (pinfunction "S_2") (pintype "passive"))
      (node (ref "T4") (pin "1") (pinfunction "S_1") (pintype "passive"))
      (node (ref "T4") (pin "4") (pinfunction "S_4") (pintype "passive"))
      (node (ref "T5") (pin "1") (pinfunction "S_1") (pintype "passive"))
      (node (ref "T5") (pin "4") (pinfunction "S_4") (pintype "passive"))
      (node (ref "T6") (pin "1") (pinfunction "S_1") (pintype "passive"))
      (node (ref "T6") (pin "4") (pinfunction "S_4") (pintype "passive"))
      (node (ref "T7") (pin "1") (pinfunction "S_1") (pintype "passive"))
      (node (ref "UART") (pin "1") (pinfunction "1_1") (pintype "passive"))
      (node (ref "USB") (pin "GND") (pinfunction "GND_GND") (pintype "power_in"))
    )
    (net (code "10") (name "J1_D15_A0") (class "Default")
      (node (ref "D13") (pin "3") (pinfunction "CA_3") (pintype "passive"))
      (node (ref "IC1") (pin "31") (pinfunction "(DAC/AIN0)PA02_31") (pintype "bidirectional"))
      (node (ref "R24") (pin "2") (pinfunction "2_2") (pintype "passive"))
      (node (ref "R25") (pin "2") (pinfunction "2_2") (pintype "passive"))
      (node (ref "T7") (pin "2") (pinfunction "G_2") (pintype "passive"))
    )
    (net (code "11") (name "J2_D25_A7{slash}AREF") (class "Default")
      (node (ref "D12") (pin "3") (pinfunction "CA_3") (pintype "passive"))
      (node (ref "IC1") (pin "33") (pinfunction "(REFA/AIN1)PA03_33") (pintype "bidirectional"))
      (node (ref "R27") (pin "2") (pinfunction "2_2") (pintype "passive"))
      (node (ref "R28") (pin "2") (pinfunction "2_2") (pintype "passive"))
      (node (ref "T6") (pin "2") (pinfunction "G_2") (pintype "passive"))
    )
    (net (code "12") (name "J3_D18_A3") (class "Default")
      (node (ref "D11") (pin "3") (pinfunction "CA_3") (pintype "passive"))
      (node (ref "IC1") (pin "34") (pinfunction "(S0:0/T0:0/REFB/AIN4)PA04_34") (pintype "bidirectional"))
      (node (ref "R30") (pin "2") (pinfunction "2_2") (pintype "passive"))
      (node (ref "R31") (pin "2") (pinfunction "2_2") (pintype "passive"))
      (node (ref "T6") (pin "5") (pinfunction "G_5") (pintype "passive"))
    )
    (net (code "13") (name "J4_D19_A4") (class "Default")
      (node (ref "D10") (pin "3") (pinfunction "CA_3") (pintype "passive"))
      (node (ref "IC1") (pin "35") (pinfunction "(S0:1/T0:1/AIN5)PA05_35") (pintype "bidirectional"))
      (node (ref "R33") (pin "2") (pinfunction "2_2") (pintype "passive"))
      (node (ref "R34") (pin "2") (pinfunction "2_2") (pintype "passive"))
      (node (ref "T5") (pin "2") (pinfunction "G_2") (pintype "passive"))
    )
    (net (code "14") (name "J5_D20_A5") (class "Default")
      (node (ref "D9") (pin "3") (pinfunction "CA_3") (pintype "passive"))
      (node (ref "IC1") (pin "36") (pinfunction "(S0:2/T1:0/AIN6)PA06_36") (pintype "bidirectional"))
      (node (ref "R36") (pin "2") (pinfunction "2_2") (pintype "passive"))
      (node (ref "R37") (pin "2") (pinfunction "2_2") (pintype "passive"))
      (node (ref "T5") (pin "5") (pinfunction "G_5") (pintype "passive"))
    )
    (net (code "15") (name "J6_D21_A6") (class "Default")
      (node (ref "D8") (pin "3") (pinfunction "CA_3") (pintype "passive"))
      (node (ref "IC1") (pin "37") (pinfunction "(S0:3/T1:1/AIN7)PA07_37") (pintype "bidirectional"))
      (node (ref "R39") (pin "2") (pinfunction "2_2") (pintype "passive"))
      (node (ref "R40") (pin "2") (pinfunction "2_2") (pintype "passive"))
      (node (ref "T4") (pin "2") (pinfunction "G_2") (pintype "passive"))
    )
    (net (code "16") (name "J7_D16_A1") (class "Default")
      (node (ref "D7") (pin "3") (pinfunction "CA_3") (pintype "passive"))
      (node (ref "IC1") (pin "27") (pinfunction "(S5:0/T6:0/AIN10)PB02_27") (pintype "bidirectional"))
      (node (ref "R42") (pin "2") (pinfunction "2_2") (pintype "passive"))
      (node (ref "R43") (pin "2") (pinfunction "2_2") (pintype "passive"))
      (node (ref "T4") (pin "5") (pinfunction "G_5") (pintype "passive"))
    )
    (net (code "17") (name "LED_SWDIO_D37") (class "Default")
      (node (ref "IC1") (pin "26") (pinfunction "(SWDIO/S1:3/T1:1)PA31_26") (pintype "bidirectional"))
      (node (ref "R14") (pin "1") (pinfunction "1_1") (pintype "passive"))
      (node (ref "SWDIO") (pin "1") (pinfunction "P_1") (pintype "passive"))
    )
    (net (code "18") (name "M1A_D7") (class "Default")
      (node (ref "IC1") (pin "14") (pinfunction "(S5:3|3:3/T7:1|0:7)PA21_14") (pintype "bidirectional"))
      (node (ref "IC3") (pin "4") (pinfunction "IN3_4") (pintype "bidirectional"))
    )
    (net (code "19") (name "M1B_D6") (class "Default")
      (node (ref "IC1") (pin "13") (pinfunction "(S5:2|3:2/T7:0|0:6)PA20_13") (pintype "bidirectional"))
      (node (ref "IC3") (pin "5") (pinfunction "IN4_5") (pintype "bidirectional"))
    )
    (net (code "20") (name "M2A_D1") (class "Default")
      (node (ref "IC1") (pin "16") (pinfunction "(SCL/S3:1|5:1/T4:1|0:5)PA23_16") (pintype "bidirectional"))
      (node (ref "IC3") (pin "1") (pinfunction "IN1_1") (pintype "bidirectional"))
    )
    (net (code "21") (name "M2B_D0") (class "Default")
      (node (ref "IC1") (pin "15") (pinfunction "(SDA/S3:0|5:0/T4:0|0:4)PA22_15") (pintype "bidirectional"))
      (node (ref "IC3") (pin "2") (pinfunction "IN2_2") (pintype "bidirectional"))
    )
    (net (code "22") (name "M3A_D3") (class "Default")
      (node (ref "IC1") (pin "41") (pinfunction "(S0:3|2:3/T1:1|0:3/AIN19)PA11_41") (pintype "bidirectional"))
      (node (ref "IC4") (pin "4") (pinfunction "IN3_4") (pintype "bidirectional"))
    )
    (net (code "23") (name "M3B_D2") (class "Default")
      (node (ref "IC1") (pin "40") (pinfunction "(S0:2|2:2/T1:0|0:2/AIN18)PA10_40") (pintype "bidirectional"))
      (node (ref "IC4") (pin "5") (pinfunction "IN4_5") (pintype "bidirectional"))
    )
    (net (code "24") (name "M4A_D5") (class "Default")
      (node (ref "IC1") (pin "44") (pinfunction "(S4:3/T5:1|0:5)PB11_44") (pintype "bidirectional"))
      (node (ref "IC4") (pin "1") (pinfunction "IN1_1") (pintype "bidirectional"))
    )
    (net (code "25") (name "M4B_D4") (class "Default")
      (node (ref "IC1") (pin "43") (pinfunction "(S4:2/T5:0|0:4)PB10_43") (pintype "bidirectional"))
      (node (ref "IC4") (pin "2") (pinfunction "IN2_2") (pintype "bidirectional"))
    )
    (net (code "26") (name "MISO_D10_LV") (class "Default")
      (node (ref "IC1") (pin "12") (pinfunction "(S1:3|3:3/T3:1|0:3)PA19_12") (pintype "bidirectional"))
      (node (ref "R19") (pin "1") (pinfunction "1_1") (pintype "passive"))
    )
    (net (code "27") (name "MISO_HV") (class "Default")
      (node (ref "IC2") (pin "6") (pinfunction "A3_6") (pintype "input"))
      (node (ref "SPI") (pin "3") (pinfunction "3_3") (pintype "passive"))
    )
    (net (code "28") (name "MOSI_D8_LV") (class "Default")
      (node (ref "IC1") (pin "8") (pinfunction "(SDA/S1:0|3:0/T2:0|0:6)PA16_8") (pintype "bidirectional"))
      (node (ref "IC2") (pin "2") (pinfunction "A1_2") (pintype "input"))
    )
    (net (code "29") (name "MOSI_HV") (class "Default")
      (node (ref "IC2") (pin "18") (pinfunction "Y1_18") (pintype "tri_state"))
      (node (ref "SPI") (pin "4") (pinfunction "4_4") (pintype "passive"))
    )
    (net (code "30") (name "Net-(C5-Pad2)") (class "Default")
      (node (ref "C5") (pin "2") (pinfunction "2_2") (pintype "passive"))
      (node (ref "R3") (pin "1") (pinfunction "1_1") (pintype "passive"))
    )
    (net (code "31") (name "Net-(IC1-(XIN32{slash}S1:0{slash}T2:0)PA00)") (class "Default")
      (node (ref "C17") (pin "1") (pinfunction "1_1") (pintype "passive"))
      (node (ref "IC1") (pin "29") (pinfunction "(XIN32/S1:0/T2:0)PA00_29") (pintype "bidirectional"))
      (node (ref "Q1") (pin "2") (pinfunction "2_2") (pintype "passive"))
    )
    (net (code "32") (name "Net-(IC1-(XOUT32{slash}S1:1{slash}T2:1)PA01)") (class "Default")
      (node (ref "C18") (pin "1") (pinfunction "1_1") (pintype "passive"))
      (node (ref "IC1") (pin "30") (pinfunction "(XOUT32/S1:1/T2:1)PA01_30") (pintype "bidirectional"))
      (node (ref "Q1") (pin "1") (pinfunction "1_1") (pintype "passive"))
    )
    (net (code "33") (name "Net-(IC1-1{slash}RTC)") (class "Default")
      (node (ref "IC1") (pin "5") (pinfunction "1/RTC_5") (pintype "bidirectional"))
      (node (ref "TP7") (pin "1") (pinfunction "P_1") (pintype "passive"))
    )
    (net (code "34") (name "Net-(IC1-4{slash}15)") (class "Default")
      (node (ref "IC1") (pin "45") (pinfunction "4/15_45") (pintype "bidirectional"))
      (node (ref "TP8") (pin "1") (pinfunction "P_1") (pintype "passive"))
    )
    (net (code "35") (name "Net-(IC1-5{slash}16{slash}LEDG)") (class "Default")
      (node (ref "IC1") (pin "46") (pinfunction "5/16/LEDG_46") (pintype "bidirectional"))
      (node (ref "R10") (pin "1") (pinfunction "1_1") (pintype "passive"))
    )
    (net (code "36") (name "Net-(IC1-6{slash}18{slash}LEDR)") (class "Default")
      (node (ref "IC1") (pin "47") (pinfunction "6/18/LEDR_47") (pintype "bidirectional"))
      (node (ref "R11") (pin "1") (pinfunction "1_1") (pintype "passive"))
    )
    (net (code "37") (name "Net-(IC1-CHIP_EN)") (class "Default")
      (node (ref "IC1") (pin "4") (pinfunction "CHIP_EN_4") (pintype "input"))
      (node (ref "TP1") (pin "1") (pinfunction "P_1") (pintype "passive"))
    )
    (net (code "38") (name "Net-(IC1-RXD)") (class "Default")
      (node (ref "IC1") (pin "3") (pinfunction "RXD_3") (pintype "input"))
      (node (ref "TP4") (pin "1") (pinfunction "P_1") (pintype "passive"))
    )
    (net (code "39") (name "Net-(IC1-SCL)") (class "Default")
      (node (ref "IC1") (pin "48") (pinfunction "SCL_48") (pintype "bidirectional"))
      (node (ref "TP5") (pin "1") (pinfunction "P_1") (pintype "passive"))
    )
    (net (code "40") (name "Net-(IC1-SDA)") (class "Default")
      (node (ref "IC1") (pin "49") (pinfunction "SDA_49") (pintype "bidirectional"))
      (node (ref "TP6") (pin "1") (pinfunction "P_1") (pintype "passive"))
    )
    (net (code "41") (name "Net-(IC1-TXD)") (class "Default")
      (node (ref "IC1") (pin "2") (pinfunction "TXD_2") (pintype "output"))
      (node (ref "TP3") (pin "1") (pinfunction "P_1") (pintype "passive"))
    )
    (net (code "42") (name "Net-(IC1-W~{RESET})") (class "Default")
      (node (ref "IC1") (pin "50") (pinfunction "W~{RESET}_50") (pintype "input"))
      (node (ref "TP2") (pin "1") (pinfunction "P_1") (pintype "passive"))
    )
    (net (code "43") (name "Net-(IC2A-Y3)") (class "Default")
      (node (ref "IC2") (pin "14") (pinfunction "Y3_14") (pintype "tri_state"))
      (node (ref "R19") (pin "2") (pinfunction "2_2") (pintype "passive"))
    )
    (net (code "44") (name "Net-(IC2B-Y3)") (class "Default")
      (node (ref "IC2") (pin "5") (pinfunction "Y3_5") (pintype "tri_state"))
      (node (ref "R20") (pin "2") (pinfunction "2_2") (pintype "passive"))
    )
    (net (code "45") (name "Net-(IC3-OUT1)") (class "Default")
      (node (ref "IC3") (pin "10") (pinfunction "OUT1_10") (pintype "passive"))
      (node (ref "M2") (pin "2") (pinfunction "1_2") (pintype "passive"))
    )
    (net (code "46") (name "Net-(IC3-OUT2)") (class "Default")
      (node (ref "IC3") (pin "9") (pinfunction "OUT2_9") (pintype "passive"))
      (node (ref "M2") (pin "1") (pinfunction "2_1") (pintype "passive"))
    )
    (net (code "47") (name "Net-(IC3-OUT3)") (class "Default")
      (node (ref "IC3") (pin "7") (pinfunction "OUT3_7") (pintype "passive"))
      (node (ref "M1") (pin "2") (pinfunction "1_2") (pintype "passive"))
    )
    (net (code "48") (name "Net-(IC3-OUT4)") (class "Default")
      (node (ref "IC3") (pin "6") (pinfunction "OUT4_6") (pintype "passive"))
      (node (ref "M1") (pin "1") (pinfunction "2_1") (pintype "passive"))
    )
    (net (code "49") (name "Net-(IC4-OUT1)") (class "Default")
      (node (ref "IC4") (pin "10") (pinfunction "OUT1_10") (pintype "passive"))
      (node (ref "M4") (pin "2") (pinfunction "1_2") (pintype "passive"))
    )
    (net (code "50") (name "Net-(IC4-OUT2)") (class "Default")
      (node (ref "IC4") (pin "9") (pinfunction "OUT2_9") (pintype "passive"))
      (node (ref "M4") (pin "1") (pinfunction "2_1") (pintype "passive"))
    )
    (net (code "51") (name "Net-(IC4-OUT3)") (class "Default")
      (node (ref "IC4") (pin "7") (pinfunction "OUT3_7") (pintype "passive"))
      (node (ref "M3") (pin "2") (pinfunction "1_2") (pintype "passive"))
    )
    (net (code "52") (name "Net-(IC4-OUT4)") (class "Default")
      (node (ref "IC4") (pin "6") (pinfunction "OUT4_6") (pintype "passive"))
      (node (ref "M3") (pin "1") (pinfunction "2_1") (pintype "passive"))
    )
    (net (code "53") (name "Net-(IC6-BOOST)") (class "Default")
      (node (ref "C4") (pin "2") (pinfunction "2_2") (pintype "passive"))
      (node (ref "IC6") (pin "1") (pinfunction "BOOST_1") (pintype "passive"))
    )
    (net (code "54") (name "Net-(IC6-COMP)") (class "Default")
      (node (ref "IC6") (pin "6") (pinfunction "COMP_6") (pintype "passive"))
      (node (ref "R3") (pin "2") (pinfunction "2_2") (pintype "passive"))
    )
    (net (code "55") (name "Net-(IC6-EN)") (class "Default")
      (node (ref "IC6") (pin "7") (pinfunction "EN_7") (pintype "input"))
      (node (ref "R1") (pin "1") (pinfunction "1_1") (pintype "passive"))
      (node (ref "R2") (pin "2") (pinfunction "2_2") (pintype "passive"))
    )
    (net (code "56") (name "Net-(IC6-FB)") (class "Default")
      (node (ref "IC6") (pin "5") (pinfunction "FB_5") (pintype "passive"))
      (node (ref "R4") (pin "1") (pinfunction "1_1") (pintype "passive"))
      (node (ref "R5") (pin "2") (pinfunction "2_2") (pintype "passive"))
    )
    (net (code "57") (name "Net-(IC6-SS)") (class "Default")
      (node (ref "C3") (pin "2") (pinfunction "2_2") (pintype "passive"))
      (node (ref "IC6") (pin "8") (pinfunction "SS_8") (pintype "passive"))
    )
    (net (code "58") (name "Net-(IC6-SW)") (class "Default")
      (node (ref "C4") (pin "1") (pinfunction "1_1") (pintype "passive"))
      (node (ref "IC6") (pin "3") (pinfunction "SW_3") (pintype "passive"))
      (node (ref "L1") (pin "1") (pinfunction "1_1") (pintype "passive"))
    )
    (net (code "59") (name "Net-(IC6-VIN)") (class "Default")
      (node (ref "C1") (pin "2") (pinfunction "2_2") (pintype "passive"))
      (node (ref "C2") (pin "2") (pinfunction "2_2") (pintype "passive"))
      (node (ref "D1") (pin "C") (pinfunction "C_C") (pintype "passive"))
      (node (ref "D2") (pin "C") (pinfunction "C_C") (pintype "passive"))
      (node (ref "F1") (pin "1") (pinfunction "1_1") (pintype "passive"))
      (node (ref "IC6") (pin "2") (pinfunction "VIN_2") (pintype "power_in"))
      (node (ref "R1") (pin "2") (pinfunction "2_2") (pintype "passive"))
    )
    (net (code "60") (name "Net-(J1-Pad3)") (class "Default")
      (node (ref "J1") (pin "3") (pinfunction "3_3") (pintype "passive"))
      (node (ref "R24") (pin "1") (pinfunction "1_1") (pintype "passive"))
    )
    (net (code "61") (name "Net-(J2-Pad3)") (class "Default")
      (node (ref "J2") (pin "3") (pinfunction "3_3") (pintype "passive"))
      (node (ref "R27") (pin "1") (pinfunction "1_1") (pintype "passive"))
    )
    (net (code "62") (name "Net-(J3-Pad3)") (class "Default")
      (node (ref "J3") (pin "3") (pinfunction "3_3") (pintype "passive"))
      (node (ref "R30") (pin "1") (pinfunction "1_1") (pintype "passive"))
    )
    (net (code "63") (name "Net-(J4-Pad3)") (class "Default")
      (node (ref "J4") (pin "3") (pinfunction "3_3") (pintype "passive"))
      (node (ref "R33") (pin "1") (pinfunction "1_1") (pintype "passive"))
    )
    (net (code "64") (name "Net-(J5-Pad3)") (class "Default")
      (node (ref "J5") (pin "3") (pinfunction "3_3") (pintype "passive"))
      (node (ref "R36") (pin "1") (pinfunction "1_1") (pintype "passive"))
    )
    (net (code "65") (name "Net-(J6-Pad3)") (class "Default")
      (node (ref "J6") (pin "3") (pinfunction "3_3") (pintype "passive"))
      (node (ref "R39") (pin "1") (pinfunction "1_1") (pintype "passive"))
    )
    (net (code "66") (name "Net-(J7-Pad3)") (class "Default")
      (node (ref "J7") (pin "3") (pinfunction "3_3") (pintype "passive"))
      (node (ref "R42") (pin "1") (pinfunction "1_1") (pintype "passive"))
    )
    (net (code "67") (name "Net-(LED1-PadA)") (class "Default")
      (node (ref "LED1") (pin "A") (pinfunction "A_A") (pintype "passive"))
      (node (ref "R26") (pin "1") (pinfunction "1_1") (pintype "passive"))
    )
    (net (code "68") (name "Net-(LED2-PadA)") (class "Default")
      (node (ref "LED2") (pin "A") (pinfunction "A_A") (pintype "passive"))
      (node (ref "R29") (pin "1") (pinfunction "1_1") (pintype "passive"))
    )
    (net (code "69") (name "Net-(LED3-PadA)") (class "Default")
      (node (ref "LED3") (pin "A") (pinfunction "A_A") (pintype "passive"))
      (node (ref "R32") (pin "1") (pinfunction "1_1") (pintype "passive"))
    )
    (net (code "70") (name "Net-(LED4-PadA)") (class "Default")
      (node (ref "LED4") (pin "A") (pinfunction "A_A") (pintype "passive"))
      (node (ref "R35") (pin "1") (pinfunction "1_1") (pintype "passive"))
    )
    (net (code "71") (name "Net-(LED5-PadA)") (class "Default")
      (node (ref "LED5") (pin "A") (pinfunction "A_A") (pintype "passive"))
      (node (ref "R38") (pin "1") (pinfunction "1_1") (pintype "passive"))
    )
    (net (code "72") (name "Net-(LED6-PadA)") (class "Default")
      (node (ref "LED6") (pin "A") (pinfunction "A_A") (pintype "passive"))
      (node (ref "R41") (pin "1") (pinfunction "1_1") (pintype "passive"))
    )
    (net (code "73") (name "Net-(LED7-PadA)") (class "Default")
      (node (ref "LED7") (pin "A") (pinfunction "A_A") (pintype "passive"))
      (node (ref "R44") (pin "1") (pinfunction "1_1") (pintype "passive"))
    )
    (net (code "74") (name "Net-(LED8-PadA)") (class "Default")
      (node (ref "LED8") (pin "A") (pinfunction "A_A") (pintype "passive"))
      (node (ref "R22") (pin "2") (pinfunction "2_2") (pintype "passive"))
    )
    (net (code "75") (name "Net-(LED9-PadA)") (class "Default")
      (node (ref "LED9") (pin "A") (pinfunction "A_A") (pintype "passive"))
      (node (ref "R14") (pin "2") (pinfunction "2_2") (pintype "passive"))
    )
    (net (code "76") (name "Net-(LED16-PadA)") (class "Default")
      (node (ref "LED16") (pin "A") (pinfunction "A_A") (pintype "passive"))
      (node (ref "R10") (pin "2") (pinfunction "2_2") (pintype "passive"))
    )
    (net (code "77") (name "Net-(LED18-PadA)") (class "Default")
      (node (ref "LED18") (pin "A") (pinfunction "A_A") (pintype "passive"))
      (node (ref "R11") (pin "2") (pinfunction "2_2") (pintype "passive"))
    )
    (net (code "78") (name "Net-(R6-Pad2)") (class "Default")
      (node (ref "R6") (pin "2") (pinfunction "2_2") (pintype "passive"))
      (node (ref "USB") (pin "SHLD1") (pinfunction "SHIELD_SHLD1") (pintype "passive"))
      (node (ref "USB") (pin "SHLD2") (pinfunction "SHIELD_SHLD2") (pintype "passive"))
      (node (ref "USB") (pin "SHLD3") (pinfunction "SHIELD_SHLD3") (pintype "passive"))
    )
    (net (code "79") (name "Net-(R45-Pad2)") (class "Default")
      (node (ref "R45") (pin "2") (pinfunction "2_2") (pintype "passive"))
      (node (ref "RESET") (pin "2") (pinfunction "S1_2") (pintype "passive"))
      (node (ref "RESET") (pin "3") (pinfunction "S1_3") (pintype "passive"))
    )
    (net (code "80") (name "Net-(S1-2)") (class "Default")
      (node (ref "D6") (pin "A") (pinfunction "A_A") (pintype "passive"))
      (node (ref "S1") (pin "1") (pinfunction "2_1") (pintype "passive"))
      (node (ref "T2") (pin "3") (pinfunction "D_3") (pintype "passive"))
    )
    (net (code "81") (name "Net-(T1-D)") (class "Default")
      (node (ref "F2") (pin "2") (pinfunction "2_2") (pintype "passive"))
      (node (ref "T1") (pin "3") (pinfunction "D_3") (pintype "passive"))
    )
    (net (code "82") (name "Net-(T1-G)") (class "Default")
      (node (ref "R7") (pin "2") (pinfunction "2_2") (pintype "passive"))
      (node (ref "R8") (pin "1") (pinfunction "1_1") (pintype "passive"))
      (node (ref "T1") (pin "1") (pinfunction "G_1") (pintype "passive"))
    )
    (net (code "83") (name "Net-(T2-G)") (class "Default")
      (node (ref "R21") (pin "2") (pinfunction "2_2") (pintype "passive"))
      (node (ref "R22") (pin "1") (pinfunction "1_1") (pintype "passive"))
      (node (ref "R23") (pin "2") (pinfunction "2_2") (pintype "passive"))
      (node (ref "T2") (pin "1") (pinfunction "G_1") (pintype "passive"))
    )
    (net (code "84") (name "Net-(T4A-D)") (class "Default")
      (node (ref "LED6") (pin "C") (pinfunction "C_C") (pintype "passive"))
      (node (ref "T4") (pin "6") (pinfunction "D_6") (pintype "passive"))
    )
    (net (code "85") (name "Net-(T4B-D)") (class "Default")
      (node (ref "LED7") (pin "C") (pinfunction "C_C") (pintype "passive"))
      (node (ref "T4") (pin "3") (pinfunction "D_3") (pintype "passive"))
    )
    (net (code "86") (name "Net-(T5A-D)") (class "Default")
      (node (ref "LED4") (pin "C") (pinfunction "C_C") (pintype "passive"))
      (node (ref "T5") (pin "6") (pinfunction "D_6") (pintype "passive"))
    )
    (net (code "87") (name "Net-(T5B-D)") (class "Default")
      (node (ref "LED5") (pin "C") (pinfunction "C_C") (pintype "passive"))
      (node (ref "T5") (pin "3") (pinfunction "D_3") (pintype "passive"))
    )
    (net (code "88") (name "Net-(T6A-D)") (class "Default")
      (node (ref "LED2") (pin "C") (pinfunction "C_C") (pintype "passive"))
      (node (ref "T6") (pin "6") (pinfunction "D_6") (pintype "passive"))
    )
    (net (code "89") (name "Net-(T6B-D)") (class "Default")
      (node (ref "LED3") (pin "C") (pinfunction "C_C") (pintype "passive"))
      (node (ref "T6") (pin "3") (pinfunction "D_3") (pintype "passive"))
    )
    (net (code "90") (name "Net-(T7A-D)") (class "Default")
      (node (ref "LED1") (pin "C") (pinfunction "C_C") (pintype "passive"))
      (node (ref "T7") (pin "6") (pinfunction "D_6") (pintype "passive"))
    )
    (net (code "91") (name "RST") (class "Default")
      (node (ref "C14") (pin "2") (pinfunction "2_2") (pintype "passive"))
      (node (ref "IC1") (pin "24") (pinfunction "~{RESET}_24") (pintype "input"))
      (node (ref "R45") (pin "1") (pinfunction "1_1") (pintype "passive"))
      (node (ref "R9") (pin "2") (pinfunction "2_2") (pintype "passive"))
      (node (ref "RST") (pin "1") (pinfunction "P_1") (pintype "passive"))
    )
    (net (code "92") (name "RX_D13_LV") (class "Default")
      (node (ref "IC1") (pin "23") (pinfunction "(S5:3/T7:1)PB23_23") (pintype "bidirectional"))
      (node (ref "R20") (pin "1") (pinfunction "1_1") (pintype "passive"))
    )
    (net (code "93") (name "RX_HV") (class "Default")
      (node (ref "IC2") (pin "15") (pinfunction "A3_15") (pintype "input"))
      (node (ref "UART") (pin "3") (pinfunction "3_3") (pintype "passive"))
    )
    (net (code "94") (name "S1_SWCLK_D36") (class "Default")
      (node (ref "IC1") (pin "25") (pinfunction "(SWCLK/S1:2/T1:0)PA30_25") (pintype "bidirectional"))
      (node (ref "R21") (pin "1") (pinfunction "1_1") (pintype "passive"))
      (node (ref "SWCLK") (pin "1") (pinfunction "P_1") (pintype "passive"))
    )
    (net (code "95") (name "SCK_D9_LV") (class "Default")
      (node (ref "IC1") (pin "9") (pinfunction "(SCL/S1:1|3:1/T2:1|0:7)PA17_9") (pintype "bidirectional"))
      (node (ref "IC2") (pin "4") (pinfunction "A2_4") (pintype "input"))
    )
    (net (code "96") (name "SCK_HV") (class "Default")
      (node (ref "IC2") (pin "16") (pinfunction "Y2_16") (pintype "tri_state"))
      (node (ref "SPI") (pin "5") (pinfunction "5_5") (pintype "passive"))
    )
    (net (code "97") (name "SCL_D12_LV") (class "Default")
      (node (ref "IC1") (pin "39") (pinfunction "(SCL/S0:1|2:1/T0:1|1:3/AIN17)PA09_39") (pintype "bidirectional"))
      (node (ref "R15") (pin "1") (pinfunction "1_1") (pintype "passive"))
      (node (ref "T3") (pin "4") (pinfunction "S_4") (pintype "passive"))
    )
    (net (code "98") (name "SDA_D11_LV") (class "Default")
      (node (ref "IC1") (pin "38") (pinfunction "(SDA/S0:0|2:0/T0:0|1:2/AIN16)PA08_38") (pintype "bidirectional"))
      (node (ref "R17") (pin "1") (pinfunction "1_1") (pintype "passive"))
      (node (ref "T3") (pin "1") (pinfunction "S_1") (pintype "passive"))
    )
    (net (code "99") (name "TX_D14_LV") (class "Default")
      (node (ref "IC1") (pin "22") (pinfunction "(S5:2/T7:0)PB22_22") (pintype "bidirectional"))
      (node (ref "IC2") (pin "13") (pinfunction "A2_13") (pintype "input"))
    )
    (net (code "100") (name "TX_HV") (class "Default")
      (node (ref "IC2") (pin "7") (pinfunction "Y2_7") (pintype "tri_state"))
      (node (ref "UART") (pin "4") (pinfunction "4_4") (pintype "passive"))
    )
    (net (code "101") (name "USB_N") (class "Default")
      (node (ref "D-") (pin "1") (pinfunction "P_1") (pintype "passive"))
      (node (ref "D14") (pin "1") (pinfunction "C1_1") (pintype "passive"))
      (node (ref "IC1") (pin "18") (pinfunction "(USB_DM/S3:2|5:2/T5:0|1:2)PA24_18") (pintype "bidirectional"))
      (node (ref "USB") (pin "D-") (pinfunction "D-_D-") (pintype "bidirectional"))
    )
    (net (code "102") (name "USB_P") (class "Default")
      (node (ref "D+") (pin "1") (pinfunction "P_1") (pintype "passive"))
      (node (ref "D14") (pin "2") (pinfunction "C2_2") (pintype "passive"))
      (node (ref "IC1") (pin "19") (pinfunction "(USB_DP/S3:3|5:3/T5:1|1:3)PA25_19") (pintype "bidirectional"))
      (node (ref "USB") (pin "D+") (pinfunction "D+_D+") (pintype "bidirectional"))
    )
    (net (code "103") (name "V+") (class "Default")
      (node (ref "C19") (pin "1") (pinfunction "1_1") (pintype "passive"))
      (node (ref "C20") (pin "1") (pinfunction "1_1") (pintype "passive"))
      (node (ref "D6") (pin "C") (pinfunction "C_C") (pintype "passive"))
      (node (ref "F1") (pin "2") (pinfunction "2_2") (pintype "passive"))
      (node (ref "IC3") (pin "3") (pinfunction "VBB_3") (pintype "power_in"))
      (node (ref "IC4") (pin "3") (pinfunction "VBB_3") (pintype "power_in"))
      (node (ref "R12") (pin "1") (pinfunction "1_1") (pintype "passive"))
      (node (ref "S1") (pin "2") (pinfunction "1_2") (pintype "passive"))
    )
    (net (code "104") (name "VBUS") (class "Default")
      (node (ref "C10") (pin "2") (pinfunction "2_2") (pintype "passive"))
      (node (ref "F2") (pin "1") (pinfunction "1_1") (pintype "passive"))
      (node (ref "USB") (pin "VBUS") (pinfunction "VBUS_VBUS") (pintype "power_in"))
      (node (ref "VBUS") (pin "1") (pinfunction "P_1") (pintype "passive"))
    )
    (net (code "105") (name "VIN") (class "Default")
      (node (ref "D1") (pin "A") (pinfunction "A_A") (pintype "passive"))
      (node (ref "POWER") (pin "2") (pinfunction "1_2") (pintype "passive"))
      (node (ref "R8") (pin "2") (pinfunction "2_2") (pintype "passive"))
    )
    (net (code "106") (name "unconnected-(IC1-3{slash}NC-Pad6)") (class "Default")
      (node (ref "IC1") (pin "6") (pinfunction "3/NC_6") (pintype "bidirectional"))
    )
    (net (code "107") (name "unconnected-(IC2A-Y4-Pad12)") (class "Default")
      (node (ref "IC2") (pin "12") (pinfunction "Y4_12") (pintype "tri_state"))
    )
    (net (code "108") (name "unconnected-(IC2B-Y4-Pad3)") (class "Default")
      (node (ref "IC2") (pin "3") (pinfunction "Y4_3") (pintype "tri_state"))
    )
    (net (code "109") (name "unconnected-(USB-PadID)") (class "Default")
      (node (ref "USB") (pin "ID") (pinfunction "ID_ID") (pintype "bidirectional"))
    )
  )
)
